# visualization_breakout_2_port.net
KiCad netlist of a schematic drawn in EAGLE
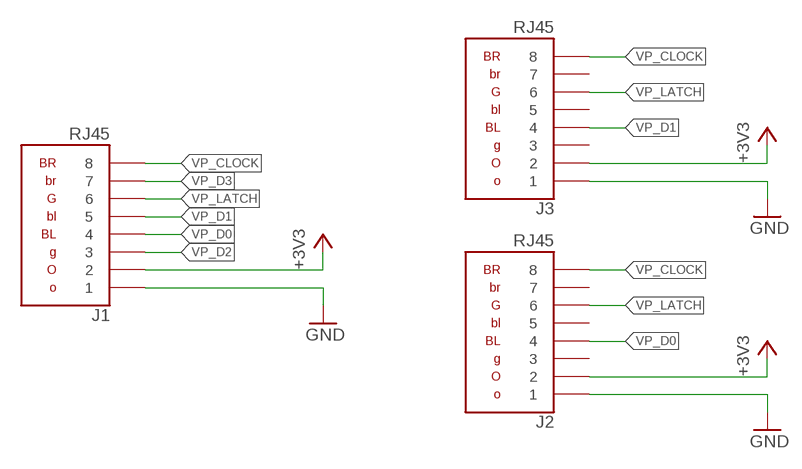
[diagram p0: schematic, sheet 1]

(export (version "E")
  (design (tool "Eeschema 10.0.6"))
  (components
    (comp (ref "J1")
      (value "RJ45")
      (footprint "eagle-import:RJ45")
      (libsource (lib "eagle-import") (part "RJ45"))
    )
    (comp (ref "J2")
      (value "RJ45")
      (footprint "eagle-import:RJ45")
      (libsource (lib "eagle-import") (part "RJ45"))
    )
    (comp (ref "J3")
      (value "RJ45")
      (footprint "eagle-import:RJ45")
      (libsource (lib "eagle-import") (part "RJ45"))
    )
  )
  (nets
    (net (code "1") (name "+3V3") (class "Default")
      (node (ref "J1") (pin "2") (pinfunction "2_2") (pintype "bidirectional"))
      (node (ref "J2") (pin "2") (pinfunction "2_2") (pintype "bidirectional"))
      (node (ref "J3") (pin "2") (pinfunction "2_2") (pintype "bidirectional"))
    )
    (net (code "2") (name "GND") (class "Default")
      (node (ref "J1") (pin "1") (pinfunction "1_1") (pintype "bidirectional"))
      (node (ref "J2") (pin "1") (pinfunction "1_1") (pintype "bidirectional"))
      (node (ref "J3") (pin "1") (pinfunction "1_1") (pintype "bidirectional"))
    )
    (net (code "3") (name "VP_CLOCK") (class "Default")
      (node (ref "J1") (pin "8") (pinfunction "8_8") (pintype "bidirectional"))
      (node (ref "J2") (pin "8") (pinfunction "8_8") (pintype "bidirectional"))
      (node (ref "J3") (pin "8") (pinfunction "8_8") (pintype "bidirectional"))
    )
    (net (code "4") (name "VP_D0") (class "Default")
      (node (ref "J1") (pin "4") (pinfunction "4_4") (pintype "bidirectional"))
      (node (ref "J2") (pin "4") (pinfunction "4_4") (pintype "bidirectional"))
    )
    (net (code "5") (name "VP_D1") (class "Default")
      (node (ref "J1") (pin "5") (pinfunction "5_5") (pintype "bidirectional"))
      (node (ref "J3") (pin "4") (pinfunction "4_4") (pintype "bidirectional"))
    )
    (net (code "6") (name "VP_D2") (class "Default")
      (node (ref "J1") (pin "3") (pinfunction "3_3") (pintype "bidirectional"))
    )
    (net (code "7") (name "VP_D3") (class "Default")
      (node (ref "J1") (pin "7") (pinfunction "7_7") (pintype "bidirectional"))
    )
    (net (code "8") (name "VP_LATCH") (class "Default")
      (node (ref "J1") (pin "6") (pinfunction "6_6") (pintype "bidirectional"))
      (node (ref "J2") (pin "6") (pinfunction "6_6") (pintype "bidirectional"))
      (node (ref "J3") (pin "6") (pinfunction "6_6") (pintype "bidirectional"))
    )
    (net (code "9") (name "unconnected-(J2-Pad3)") (class "Default")
      (node (ref "J2") (pin "3") (pinfunction "3_3") (pintype "bidirectional"))
    )
    (net (code "10") (name "unconnected-(J2-Pad5)") (class "Default")
      (node (ref "J2") (pin "5") (pinfunction "5_5") (pintype "bidirectional"))
    )
    (net (code "11") (name "unconnected-(J2-Pad7)") (class "Default")
      (node (ref "J2") (pin "7") (pinfunction "7_7") (pintype "bidirectional"))
    )
    (net (code "12") (name "unconnected-(J3-Pad3)") (class "Default")
      (node (ref "J3") (pin "3") (pinfunction "3_3") (pintype "bidirectional"))
    )
    (net (code "13") (name "unconnected-(J3-Pad5)") (class "Default")
      (node (ref "J3") (pin "5") (pinfunction "5_5") (pintype "bidirectional"))
    )
    (net (code "14") (name "unconnected-(J3-Pad7)") (class "Default")
      (node (ref "J3") (pin "7") (pinfunction "7_7") (pintype "bidirectional"))
    )
  )
)
